# demeter_v26.net
KiCad netlist of a schematic drawn in EAGLE
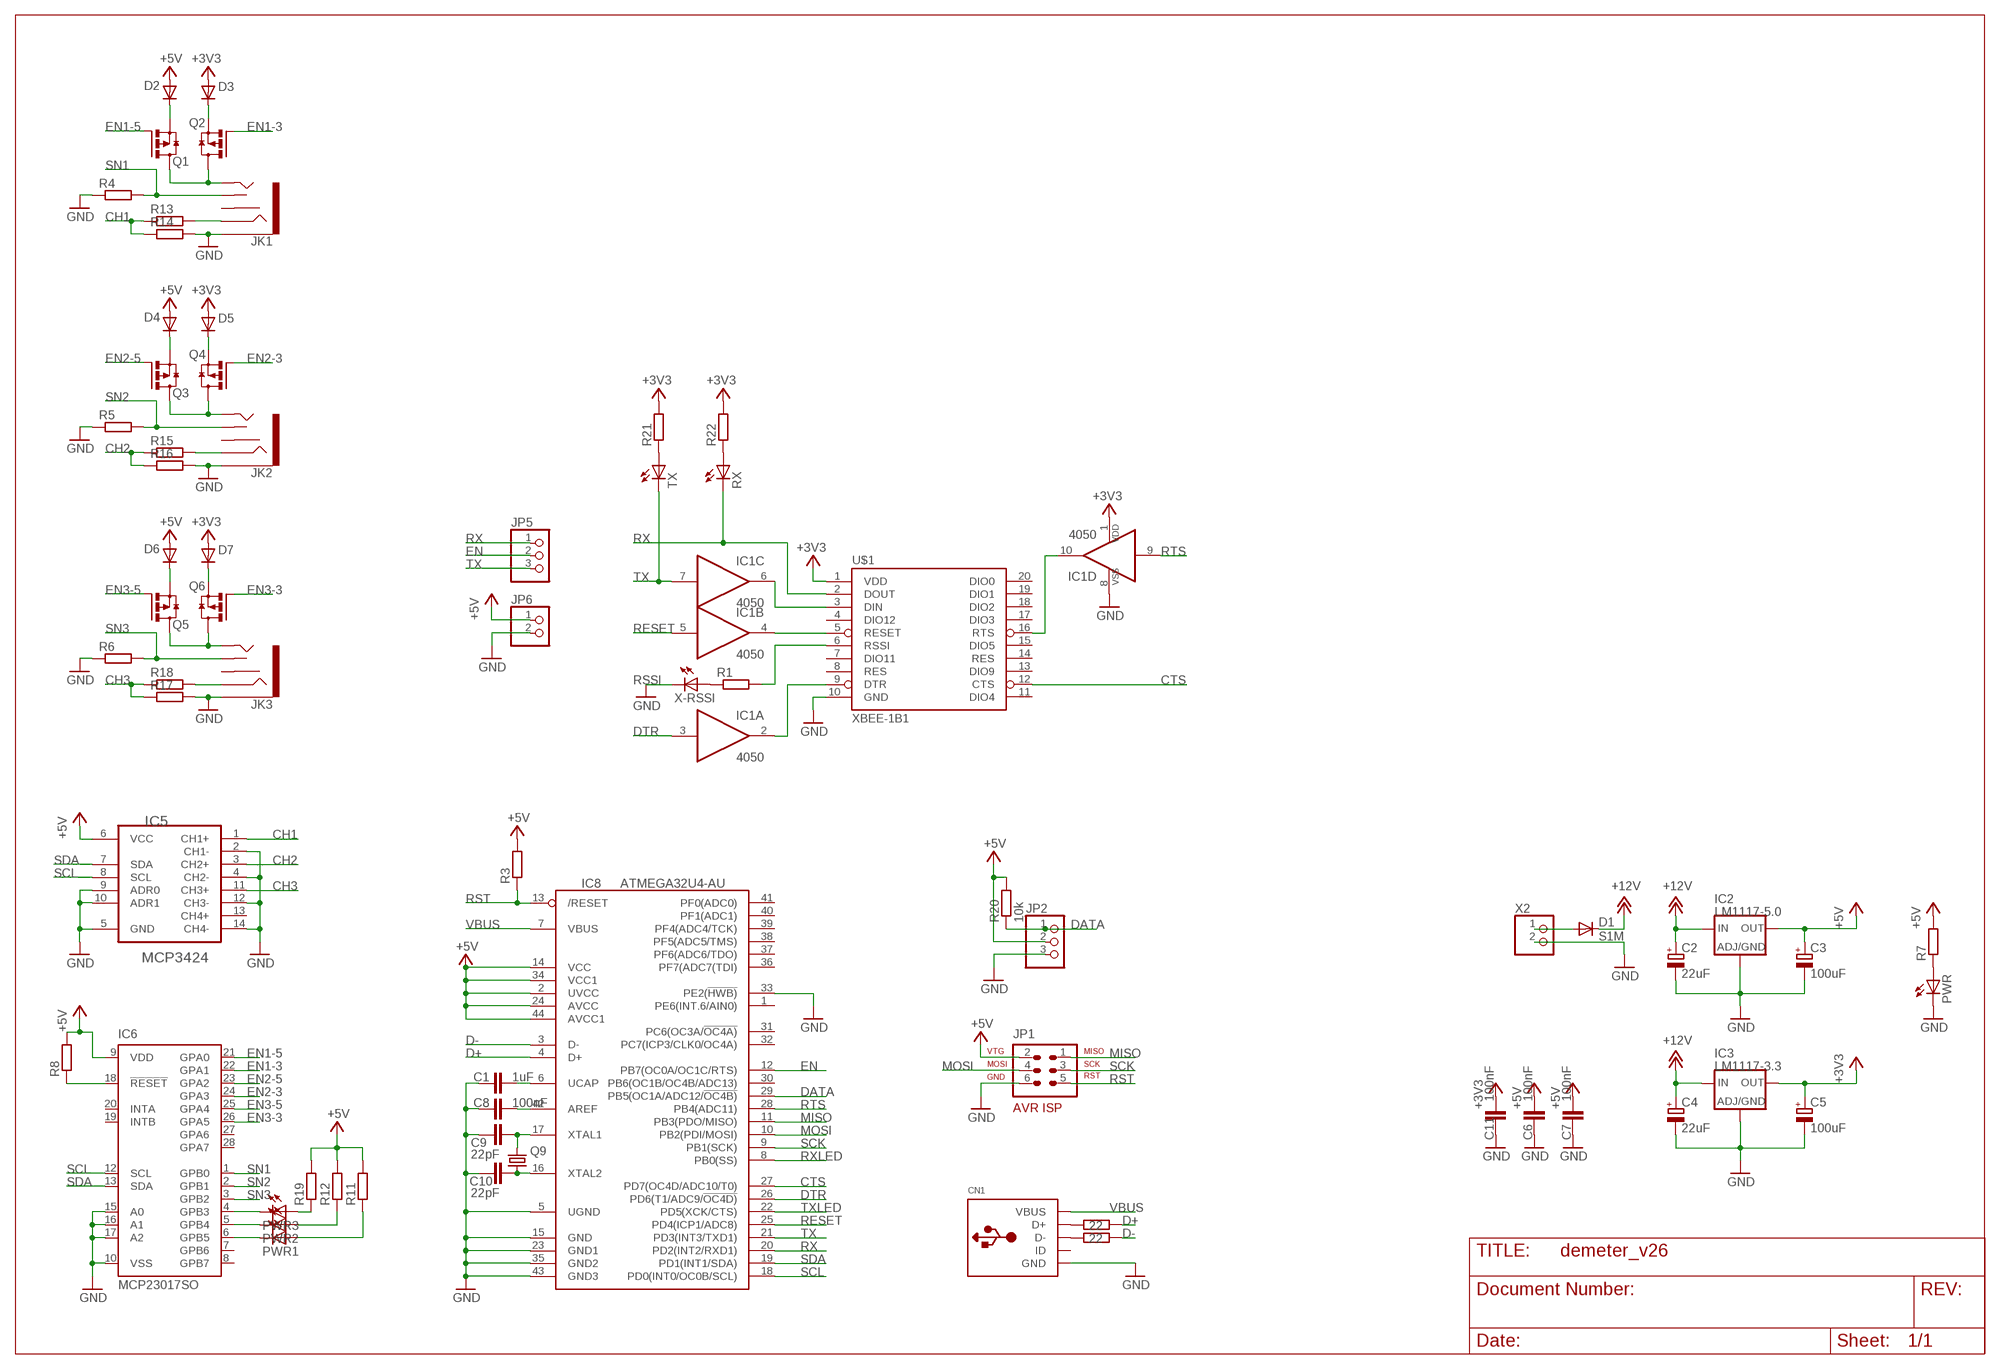
[diagram p0: schematic, sheet 1]

(export (version "E")
  (design (tool "Eeschema 10.0.6"))
  (components
    (comp (ref "C1")
      (value "1uF")
      (footprint "eagle-import:C0805K")
      (libsource (lib "eagle-import") (part "C-EUC0805K"))
    )
    (comp (ref "C2")
      (value "22uF")
      (footprint "eagle-import:PANASONIC_D")
      (libsource (lib "eagle-import") (part "CPOL-EUPD"))
    )
    (comp (ref "C3")
      (value "100uF")
      (footprint "eagle-import:PANASONIC_D")
      (libsource (lib "eagle-import") (part "CPOL-EUPD"))
    )
    (comp (ref "C4")
      (value "22uF")
      (footprint "eagle-import:PANASONIC_D")
      (libsource (lib "eagle-import") (part "CPOL-EUPD"))
    )
    (comp (ref "C5")
      (value "100uF")
      (footprint "eagle-import:PANASONIC_D")
      (libsource (lib "eagle-import") (part "CPOL-EUPD"))
    )
    (comp (ref "C6")
      (value "100nF")
      (footprint "eagle-import:C0805K")
      (libsource (lib "eagle-import") (part "C-EUC0805K"))
    )
    (comp (ref "C7")
      (value "100nF")
      (footprint "eagle-import:C0805K")
      (libsource (lib "eagle-import") (part "C-EUC0805K"))
    )
    (comp (ref "C8")
      (value "100nF")
      (footprint "eagle-import:C0805K")
      (libsource (lib "eagle-import") (part "C-EUC0805K"))
    )
    (comp (ref "C9")
      (value "22pF")
      (footprint "eagle-import:C0805K")
      (libsource (lib "eagle-import") (part "C-EUC0805K"))
    )
    (comp (ref "C10")
      (value "22pF")
      (footprint "eagle-import:C0805K")
      (libsource (lib "eagle-import") (part "C-EUC0805K"))
    )
    (comp (ref "C11")
      (value "100nF")
      (footprint "eagle-import:C0805K")
      (libsource (lib "eagle-import") (part "C-EUC0805K"))
    )
    (comp (ref "CN1")
      (value "USBMINIB")
      (footprint "eagle-import:USB-MINIB")
      (libsource (lib "eagle-import") (part "USBMINIB"))
    )
    (comp (ref "D1")
      (value "S1M")
      (footprint "eagle-import:DO-214AC")
      (libsource (lib "eagle-import") (part "S1M"))
    )
    (comp (ref "D2")
      (value "MBR0520")
      (footprint "eagle-import:SOD123")
      (libsource (lib "eagle-import") (part "MBR0520"))
    )
    (comp (ref "D3")
      (value "MBR0520")
      (footprint "eagle-import:SOD123")
      (libsource (lib "eagle-import") (part "MBR0520"))
    )
    (comp (ref "D4")
      (value "MBR0520")
      (footprint "eagle-import:SOD123")
      (libsource (lib "eagle-import") (part "MBR0520"))
    )
    (comp (ref "D5")
      (value "MBR0520")
      (footprint "eagle-import:SOD123")
      (libsource (lib "eagle-import") (part "MBR0520"))
    )
    (comp (ref "D6")
      (value "MBR0520")
      (footprint "eagle-import:SOD123")
      (libsource (lib "eagle-import") (part "MBR0520"))
    )
    (comp (ref "D7")
      (value "MBR0520")
      (footprint "eagle-import:SOD123")
      (libsource (lib "eagle-import") (part "MBR0520"))
    )
    (comp (ref "IC1")
      (value "4050")
      (footprint "eagle-import:SO16")
      (libsource (lib "eagle-import") (part "4050D"))
    )
    (comp (ref "IC2")
      (value "LM1117-5.0")
      (footprint "eagle-import:DPACK")
      (libsource (lib "eagle-import") (part "LM1117DT"))
    )
    (comp (ref "IC3")
      (value "LM1117-3.3")
      (footprint "eagle-import:DPACK")
      (libsource (lib "eagle-import") (part "LM1117DT"))
    )
    (comp (ref "IC5")
      (value "MCP3424")
      (footprint "eagle-import:SO14")
      (fields (field (name "MPN") "MCP3424-E/SL"))
      (libsource (lib "eagle-import") (part "MCP3424"))
    )
    (comp (ref "IC6")
      (value "MCP23017SO")
      (footprint "eagle-import:SO28W")
      (fields (field (name "MF") "MICROCHIP") (field (name "MPN") "MCP23017-E/SO"))
      (libsource (lib "eagle-import") (part "MCP23017SO"))
    )
    (comp (ref "IC8")
      (value "ATMEGA32U4-AU")
      (footprint "eagle-import:TQFP44")
      (libsource (lib "eagle-import") (part "ATMEGA32U4-AU"))
    )
    (comp (ref "JK1")
      (value "AUDIO-JACK2PTH")
      (footprint "eagle-import:AUDIO-JACK")
      (libsource (lib "eagle-import") (part "AUDIO-JACK2PTH"))
    )
    (comp (ref "JK2")
      (value "AUDIO-JACK2PTH")
      (footprint "eagle-import:AUDIO-JACK")
      (libsource (lib "eagle-import") (part "AUDIO-JACK2PTH"))
    )
    (comp (ref "JK3")
      (value "AUDIO-JACK2PTH")
      (footprint "eagle-import:AUDIO-JACK")
      (libsource (lib "eagle-import") (part "AUDIO-JACK2PTH"))
    )
    (comp (ref "JP1")
      (value "AVR-ISP-6")
      (footprint "eagle-import:AVR-ISP-6")
      (libsource (lib "eagle-import") (part "AVR-ISP-6"))
    )
    (comp (ref "JP2")
      (value "PINHD-1X3180")
      (footprint "eagle-import:1X03")
      (libsource (lib "eagle-import") (part "PINHD-1X3180"))
    )
    (comp (ref "JP5")
      (value "PINHD-1X3180")
      (footprint "eagle-import:1X03")
      (libsource (lib "eagle-import") (part "PINHD-1X3180"))
    )
    (comp (ref "JP6")
      (value "PINHD-1X2")
      (footprint "eagle-import:1X02")
      (libsource (lib "eagle-import") (part "PINHD-1X2"))
    )
    (comp (ref "PWR")
      (value "LED0805")
      (footprint "eagle-import:CHIP-LED0805")
      (libsource (lib "eagle-import") (part "LED0805"))
    )
    (comp (ref "PWR1")
      (value "LED0805")
      (footprint "eagle-import:CHIP-LED0805")
      (libsource (lib "eagle-import") (part "LED0805"))
    )
    (comp (ref "PWR2")
      (value "LED0805")
      (footprint "eagle-import:CHIP-LED0805")
      (libsource (lib "eagle-import") (part "LED0805"))
    )
    (comp (ref "PWR3")
      (value "LED0805")
      (footprint "eagle-import:CHIP-LED0805")
      (libsource (lib "eagle-import") (part "LED0805"))
    )
    (comp (ref "Q1")
      (value "IRLML6402")
      (footprint "eagle-import:SOT23")
      (libsource (lib "eagle-import") (part "IRLML6402"))
    )
    (comp (ref "Q2")
      (value "IRLML6402")
      (footprint "eagle-import:SOT23")
      (libsource (lib "eagle-import") (part "IRLML6402"))
    )
    (comp (ref "Q3")
      (value "IRLML6402")
      (footprint "eagle-import:SOT23")
      (libsource (lib "eagle-import") (part "IRLML6402"))
    )
    (comp (ref "Q4")
      (value "IRLML6402")
      (footprint "eagle-import:SOT23")
      (libsource (lib "eagle-import") (part "IRLML6402"))
    )
    (comp (ref "Q5")
      (value "IRLML6402")
      (footprint "eagle-import:SOT23")
      (libsource (lib "eagle-import") (part "IRLML6402"))
    )
    (comp (ref "Q6")
      (value "IRLML6402")
      (footprint "eagle-import:SOT23")
      (libsource (lib "eagle-import") (part "IRLML6402"))
    )
    (comp (ref "Q9")
      (value "CRYSTALHC49UP")
      (footprint "eagle-import:HC49UP")
      (libsource (lib "eagle-import") (part "CRYSTALHC49UP"))
    )
    (comp (ref "R1")
      (value "R-EU_R0805")
      (footprint "eagle-import:R0805")
      (libsource (lib "eagle-import") (part "R-EU_R0805"))
    )
    (comp (ref "R3")
      (value "R-EU_R0805")
      (footprint "eagle-import:R0805")
      (libsource (lib "eagle-import") (part "R-EU_R0805"))
    )
    (comp (ref "R4")
      (value "R-EU_R0805")
      (footprint "eagle-import:R0805")
      (libsource (lib "eagle-import") (part "R-EU_R0805"))
    )
    (comp (ref "R5")
      (value "R-EU_R0805")
      (footprint "eagle-import:R0805")
      (libsource (lib "eagle-import") (part "R-EU_R0805"))
    )
    (comp (ref "R6")
      (value "R-EU_R0805")
      (footprint "eagle-import:R0805")
      (libsource (lib "eagle-import") (part "R-EU_R0805"))
    )
    (comp (ref "R7")
      (value "R-EU_R0805")
      (footprint "eagle-import:R0805")
      (libsource (lib "eagle-import") (part "R-EU_R0805"))
    )
    (comp (ref "R8")
      (value "R-EU_R0805")
      (footprint "eagle-import:R0805")
      (libsource (lib "eagle-import") (part "R-EU_R0805"))
    )
    (comp (ref "R9")
      (value "22")
      (footprint "eagle-import:R0805")
      (libsource (lib "eagle-import") (part "R-EU_R0805"))
    )
    (comp (ref "R10")
      (value "22")
      (footprint "eagle-import:R0805")
      (libsource (lib "eagle-import") (part "R-EU_R0805"))
    )
    (comp (ref "R11")
      (value "R-EU_R0805")
      (footprint "eagle-import:R0805")
      (libsource (lib "eagle-import") (part "R-EU_R0805"))
    )
    (comp (ref "R12")
      (value "R-EU_R0805")
      (footprint "eagle-import:R0805")
      (libsource (lib "eagle-import") (part "R-EU_R0805"))
    )
    (comp (ref "R13")
      (value "R-EU_R0805")
      (footprint "eagle-import:R0805")
      (libsource (lib "eagle-import") (part "R-EU_R0805"))
    )
    (comp (ref "R14")
      (value "R-EU_R0805")
      (footprint "eagle-import:R0805")
      (libsource (lib "eagle-import") (part "R-EU_R0805"))
    )
    (comp (ref "R15")
      (value "R-EU_R0805")
      (footprint "eagle-import:R0805")
      (libsource (lib "eagle-import") (part "R-EU_R0805"))
    )
    (comp (ref "R16")
      (value "R-EU_R0805")
      (footprint "eagle-import:R0805")
      (libsource (lib "eagle-import") (part "R-EU_R0805"))
    )
    (comp (ref "R17")
      (value "R-EU_R0805")
      (footprint "eagle-import:R0805")
      (libsource (lib "eagle-import") (part "R-EU_R0805"))
    )
    (comp (ref "R18")
      (value "R-EU_R0805")
      (footprint "eagle-import:R0805")
      (libsource (lib "eagle-import") (part "R-EU_R0805"))
    )
    (comp (ref "R19")
      (value "R-EU_R0805")
      (footprint "eagle-import:R0805")
      (libsource (lib "eagle-import") (part "R-EU_R0805"))
    )
    (comp (ref "R20")
      (value "10k")
      (footprint "eagle-import:R0805")
      (libsource (lib "eagle-import") (part "R-EU_R0805"))
    )
    (comp (ref "R21")
      (value "R-EU_R0805")
      (footprint "eagle-import:R0805")
      (libsource (lib "eagle-import") (part "R-EU_R0805"))
    )
    (comp (ref "R22")
      (value "R-EU_R0805")
      (footprint "eagle-import:R0805")
      (libsource (lib "eagle-import") (part "R-EU_R0805"))
    )
    (comp (ref "RX")
      (value "LED0805")
      (footprint "eagle-import:CHIP-LED0805")
      (libsource (lib "eagle-import") (part "LED0805"))
    )
    (comp (ref "TX")
      (value "LED0805")
      (footprint "eagle-import:CHIP-LED0805")
      (libsource (lib "eagle-import") (part "LED0805"))
    )
    (comp (ref "U$1")
      (value "XBEE-1B1")
      (footprint "eagle-import:XBEE-1")
      (libsource (lib "eagle-import") (part "XBEE-1B1"))
    )
    (comp (ref "X-RSSI")
      (value "LED0805")
      (footprint "eagle-import:CHIP-LED0805")
      (libsource (lib "eagle-import") (part "LED0805"))
    )
    (comp (ref "X2")
      (value "W237-102")
      (footprint "eagle-import:W237-102")
      (libsource (lib "eagle-import") (part "W237-102"))
    )
  )
  (nets
    (net (code "1") (name "+3V3") (class "Default")
      (node (ref "C11") (pin "1") (pinfunction "1_1") (pintype "passive"))
      (node (ref "C5") (pin "+") (pinfunction "+_+") (pintype "passive"))
      (node (ref "D3") (pin "A") (pinfunction "A_A") (pintype "passive"))
      (node (ref "D5") (pin "A") (pinfunction "A_A") (pintype "passive"))
      (node (ref "D7") (pin "A") (pinfunction "A_A") (pintype "passive"))
      (node (ref "IC1") (pin "1") (pinfunction "VDD_1") (pintype "power_in"))
      (node (ref "IC3") (pin "4") (pinfunction "OUT_4") (pintype "passive"))
      (node (ref "R21") (pin "2") (pinfunction "2_2") (pintype "passive"))
      (node (ref "R22") (pin "2") (pinfunction "2_2") (pintype "passive"))
      (node (ref "U$1") (pin "1") (pinfunction "VDD_1") (pintype "power_in"))
    )
    (net (code "2") (name "+5V") (class "Default")
      (node (ref "C3") (pin "+") (pinfunction "+_+") (pintype "passive"))
      (node (ref "C6") (pin "1") (pinfunction "1_1") (pintype "passive"))
      (node (ref "C7") (pin "1") (pinfunction "1_1") (pintype "passive"))
      (node (ref "D2") (pin "A") (pinfunction "A_A") (pintype "passive"))
      (node (ref "D4") (pin "A") (pinfunction "A_A") (pintype "passive"))
      (node (ref "D6") (pin "A") (pinfunction "A_A") (pintype "passive"))
      (node (ref "IC2") (pin "4") (pinfunction "OUT_4") (pintype "passive"))
      (node (ref "IC5") (pin "6") (pinfunction "VCC_6") (pintype "power_in"))
      (node (ref "IC6") (pin "9") (pinfunction "VDD_9") (pintype "power_in"))
      (node (ref "IC8") (pin "14") (pinfunction "VCC_14") (pintype "bidirectional"))
      (node (ref "IC8") (pin "2") (pinfunction "UVCC_2") (pintype "bidirectional"))
      (node (ref "IC8") (pin "24") (pinfunction "AVCC_24") (pintype "bidirectional"))
      (node (ref "IC8") (pin "34") (pinfunction "VCC1_34") (pintype "bidirectional"))
      (node (ref "IC8") (pin "44") (pinfunction "AVCC1_44") (pintype "bidirectional"))
      (node (ref "JP1") (pin "2") (pinfunction "VTG_2") (pintype "passive"))
      (node (ref "JP2") (pin "2") (pinfunction "2_2") (pintype "passive"))
      (node (ref "JP6") (pin "1") (pinfunction "1_1") (pintype "passive"))
      (node (ref "R11") (pin "2") (pinfunction "2_2") (pintype "passive"))
      (node (ref "R12") (pin "2") (pinfunction "2_2") (pintype "passive"))
      (node (ref "R19") (pin "2") (pinfunction "2_2") (pintype "passive"))
      (node (ref "R20") (pin "2") (pinfunction "2_2") (pintype "passive"))
      (node (ref "R3") (pin "2") (pinfunction "2_2") (pintype "passive"))
      (node (ref "R7") (pin "2") (pinfunction "2_2") (pintype "passive"))
      (node (ref "R8") (pin "2") (pinfunction "2_2") (pintype "passive"))
    )
    (net (code "3") (name "+12V") (class "Default")
      (node (ref "C2") (pin "+") (pinfunction "+_+") (pintype "passive"))
      (node (ref "C4") (pin "+") (pinfunction "+_+") (pintype "passive"))
      (node (ref "D1") (pin "C") (pinfunction "C_C") (pintype "passive"))
      (node (ref "IC2") (pin "3") (pinfunction "IN_3") (pintype "input"))
      (node (ref "IC3") (pin "3") (pinfunction "IN_3") (pintype "input"))
    )
    (net (code "4") (name "/CH1") (class "Default")
      (node (ref "IC5") (pin "1") (pinfunction "CH1+_1") (pintype "input"))
      (node (ref "R13") (pin "1") (pinfunction "1_1") (pintype "passive"))
      (node (ref "R14") (pin "1") (pinfunction "1_1") (pintype "passive"))
    )
    (net (code "5") (name "/CH2") (class "Default")
      (node (ref "IC5") (pin "3") (pinfunction "CH2+_3") (pintype "input"))
      (node (ref "R15") (pin "1") (pinfunction "1_1") (pintype "passive"))
      (node (ref "R16") (pin "1") (pinfunction "1_1") (pintype "passive"))
    )
    (net (code "6") (name "/CH3") (class "Default")
      (node (ref "IC5") (pin "11") (pinfunction "CH3+_11") (pintype "input"))
      (node (ref "R17") (pin "1") (pinfunction "1_1") (pintype "passive"))
      (node (ref "R18") (pin "1") (pinfunction "1_1") (pintype "passive"))
    )
    (net (code "7") (name "/CTS") (class "Default")
      (node (ref "IC8") (pin "27") (pinfunction "PD7(OC4D/ADC10/T0)_27") (pintype "bidirectional"))
      (node (ref "U$1") (pin "12") (pinfunction "CTS_12") (pintype "output"))
    )
    (net (code "8") (name "/D+") (class "Default")
      (node (ref "IC8") (pin "4") (pinfunction "D+_4") (pintype "bidirectional"))
      (node (ref "R9") (pin "1") (pinfunction "1_1") (pintype "passive"))
    )
    (net (code "9") (name "/D-") (class "Default")
      (node (ref "IC8") (pin "3") (pinfunction "D-_3") (pintype "bidirectional"))
      (node (ref "R10") (pin "1") (pinfunction "1_1") (pintype "passive"))
    )
    (net (code "10") (name "/DATA") (class "Default")
      (node (ref "IC8") (pin "29") (pinfunction "PB5(OC1A/ADC12/~{OC4B})_29") (pintype "bidirectional"))
      (node (ref "JP2") (pin "1") (pinfunction "1_1") (pintype "passive"))
      (node (ref "R20") (pin "1") (pinfunction "1_1") (pintype "passive"))
    )
    (net (code "11") (name "/DTR") (class "Default")
      (node (ref "IC1") (pin "3") (pinfunction "I_3") (pintype "input"))
      (node (ref "IC8") (pin "26") (pinfunction "PD6(T1/ADC9/~{OC4D})_26") (pintype "bidirectional"))
    )
    (net (code "12") (name "/EN") (class "Default")
      (node (ref "IC8") (pin "12") (pinfunction "PB7(OC0A/OC1C/RTS)_12") (pintype "bidirectional"))
      (node (ref "JP5") (pin "2") (pinfunction "2_2") (pintype "passive"))
    )
    (net (code "13") (name "/EN1-3") (class "Default")
      (node (ref "IC6") (pin "22") (pinfunction "GPA1_22") (pintype "bidirectional"))
      (node (ref "Q2") (pin "1") (pinfunction "G_1") (pintype "passive"))
    )
    (net (code "14") (name "/EN1-5") (class "Default")
      (node (ref "IC6") (pin "21") (pinfunction "GPA0_21") (pintype "bidirectional"))
      (node (ref "Q1") (pin "1") (pinfunction "G_1") (pintype "passive"))
    )
    (net (code "15") (name "/EN2-3") (class "Default")
      (node (ref "IC6") (pin "24") (pinfunction "GPA3_24") (pintype "bidirectional"))
      (node (ref "Q4") (pin "1") (pinfunction "G_1") (pintype "passive"))
    )
    (net (code "16") (name "/EN2-5") (class "Default")
      (node (ref "IC6") (pin "23") (pinfunction "GPA2_23") (pintype "bidirectional"))
      (node (ref "Q3") (pin "1") (pinfunction "G_1") (pintype "passive"))
    )
    (net (code "17") (name "/EN3-3") (class "Default")
      (node (ref "IC6") (pin "26") (pinfunction "GPA5_26") (pintype "bidirectional"))
      (node (ref "Q6") (pin "1") (pinfunction "G_1") (pintype "passive"))
    )
    (net (code "18") (name "/EN3-5") (class "Default")
      (node (ref "IC6") (pin "25") (pinfunction "GPA4_25") (pintype "bidirectional"))
      (node (ref "Q5") (pin "1") (pinfunction "G_1") (pintype "passive"))
    )
    (net (code "19") (name "/MISO") (class "Default")
      (node (ref "IC8") (pin "11") (pinfunction "PB3(PDO/MISO)_11") (pintype "bidirectional"))
      (node (ref "JP1") (pin "1") (pinfunction "MISO_1") (pintype "passive"))
    )
    (net (code "20") (name "/MOSI") (class "Default")
      (node (ref "IC8") (pin "10") (pinfunction "PB2(PDI/MOSI)_10") (pintype "bidirectional"))
      (node (ref "JP1") (pin "4") (pinfunction "MOSI_4") (pintype "passive"))
    )
    (net (code "21") (name "/RESET") (class "Default")
      (node (ref "IC1") (pin "5") (pinfunction "I_5") (pintype "input"))
      (node (ref "IC8") (pin "25") (pinfunction "PD4(ICP1/ADC8)_25") (pintype "bidirectional"))
    )
    (net (code "22") (name "/RSSI") (class "Default")
      (node (ref "R1") (pin "2") (pinfunction "2_2") (pintype "passive"))
      (node (ref "U$1") (pin "6") (pinfunction "RSSI_6") (pintype "bidirectional"))
    )
    (net (code "23") (name "/RST") (class "Default")
      (node (ref "IC8") (pin "13") (pinfunction "/RESET_13") (pintype "bidirectional"))
      (node (ref "JP1") (pin "5") (pinfunction "RST_5") (pintype "passive"))
      (node (ref "R3") (pin "1") (pinfunction "1_1") (pintype "passive"))
    )
    (net (code "24") (name "/RTS") (class "Default")
      (node (ref "IC1") (pin "9") (pinfunction "I_9") (pintype "input"))
      (node (ref "IC8") (pin "28") (pinfunction "PB4(ADC11)_28") (pintype "bidirectional"))
    )
    (net (code "25") (name "/RX") (class "Default")
      (node (ref "IC8") (pin "20") (pinfunction "PD2(INT2/RXD1)_20") (pintype "bidirectional"))
      (node (ref "JP5") (pin "1") (pinfunction "1_1") (pintype "passive"))
      (node (ref "RX") (pin "C") (pinfunction "C_C") (pintype "passive"))
      (node (ref "U$1") (pin "2") (pinfunction "DOUT_2") (pintype "output"))
    )
    (net (code "26") (name "/RXLED") (class "Default")
      (node (ref "IC8") (pin "8") (pinfunction "PB0(SS)_8") (pintype "bidirectional"))
    )
    (net (code "27") (name "/SCK") (class "Default")
      (node (ref "IC8") (pin "9") (pinfunction "PB1(SCK)_9") (pintype "bidirectional"))
      (node (ref "JP1") (pin "3") (pinfunction "SCK_3") (pintype "passive"))
    )
    (net (code "28") (name "/SCL") (class "Default")
      (node (ref "IC5") (pin "8") (pinfunction "SCL_8") (pintype "input"))
      (node (ref "IC6") (pin "12") (pinfunction "SCL_12") (pintype "input"))
      (node (ref "IC8") (pin "18") (pinfunction "PD0(INT0/OC0B/SCL)_18") (pintype "bidirectional"))
    )
    (net (code "29") (name "/SDA") (class "Default")
      (node (ref "IC5") (pin "7") (pinfunction "SDA_7") (pintype "bidirectional"))
      (node (ref "IC6") (pin "13") (pinfunction "SDA_13") (pintype "bidirectional"))
      (node (ref "IC8") (pin "19") (pinfunction "PD1(INT1/SDA)_19") (pintype "bidirectional"))
    )
    (net (code "30") (name "/SN1") (class "Default")
      (node (ref "IC6") (pin "1") (pinfunction "GPB0_1") (pintype "bidirectional"))
      (node (ref "JK1") (pin "TSH") (pinfunction "TSH_TSH") (pintype "bidirectional"))
      (node (ref "R4") (pin "2") (pinfunction "2_2") (pintype "passive"))
    )
    (net (code "31") (name "/SN2") (class "Default")
      (node (ref "IC6") (pin "2") (pinfunction "GPB1_2") (pintype "bidirectional"))
      (node (ref "JK2") (pin "TSH") (pinfunction "TSH_TSH") (pintype "bidirectional"))
      (node (ref "R5") (pin "2") (pinfunction "2_2") (pintype "passive"))
    )
    (net (code "32") (name "/SN3") (class "Default")
      (node (ref "IC6") (pin "3") (pinfunction "GPB2_3") (pintype "bidirectional"))
      (node (ref "JK3") (pin "TSH") (pinfunction "TSH_TSH") (pintype "bidirectional"))
      (node (ref "R6") (pin "2") (pinfunction "2_2") (pintype "passive"))
    )
    (net (code "33") (name "/TX") (class "Default")
      (node (ref "IC1") (pin "7") (pinfunction "I_7") (pintype "input"))
      (node (ref "IC8") (pin "21") (pinfunction "PD3(INT3/TXD1)_21") (pintype "bidirectional"))
      (node (ref "JP5") (pin "3") (pinfunction "3_3") (pintype "passive"))
      (node (ref "TX") (pin "C") (pinfunction "C_C") (pintype "passive"))
    )
    (net (code "34") (name "/TXLED") (class "Default")
      (node (ref "IC8") (pin "22") (pinfunction "PD5(XCK/CTS)_22") (pintype "bidirectional"))
    )
    (net (code "35") (name "/VBUS") (class "Default")
      (node (ref "CN1") (pin "VBUS") (pinfunction "VBUS_VBUS") (pintype "power_in"))
      (node (ref "IC8") (pin "7") (pinfunction "VBUS_7") (pintype "bidirectional"))
    )
    (net (code "36") (name "GND") (class "Default")
      (node (ref "C1") (pin "2") (pinfunction "2_2") (pintype "passive"))
      (node (ref "C10") (pin "2") (pinfunction "2_2") (pintype "passive"))
      (node (ref "C11") (pin "2") (pinfunction "2_2") (pintype "passive"))
      (node (ref "C2") (pin "-") (pinfunction "-_-") (pintype "passive"))
      (node (ref "C3") (pin "-") (pinfunction "-_-") (pintype "passive"))
      (node (ref "C4") (pin "-") (pinfunction "-_-") (pintype "passive"))
      (node (ref "C5") (pin "-") (pinfunction "-_-") (pintype "passive"))
      (node (ref "C6") (pin "2") (pinfunction "2_2") (pintype "passive"))
      (node (ref "C7") (pin "2") (pinfunction "2_2") (pintype "passive"))
      (node (ref "C8") (pin "2") (pinfunction "2_2") (pintype "passive"))
      (node (ref "C9") (pin "2") (pinfunction "2_2") (pintype "passive"))
      (node (ref "CN1") (pin "GND") (pinfunction "GND_GND") (pintype "power_in"))
      (node (ref "IC1") (pin "8") (pinfunction "VSS_8") (pintype "power_in"))
      (node (ref "IC2") (pin "1") (pinfunction "ADJ_1") (pintype "input"))
      (node (ref "IC3") (pin "1") (pinfunction "ADJ_1") (pintype "input"))
      (node (ref "IC5") (pin "10") (pinfunction "ADR1_10") (pintype "input"))
      (node (ref "IC5") (pin "12") (pinfunction "CH3-_12") (pintype "input"))
      (node (ref "IC5") (pin "14") (pinfunction "CH4-_14") (pintype "input"))
      (node (ref "IC5") (pin "2") (pinfunction "CH1-_2") (pintype "input"))
      (node (ref "IC5") (pin "4") (pinfunction "CH2-_4") (pintype "input"))
      (node (ref "IC5") (pin "5") (pinfunction "GND_5") (pintype "power_in"))
      (node (ref "IC5") (pin "9") (pinfunction "ADR0_9") (pintype "input"))
      (node (ref "IC6") (pin "10") (pinfunction "VSS_10") (pintype "power_in"))
      (node (ref "IC6") (pin "15") (pinfunction "A0_15") (pintype "input"))
      (node (ref "IC6") (pin "16") (pinfunction "A1_16") (pintype "input"))
      (node (ref "IC6") (pin "17") (pinfunction "A2_17") (pintype "input"))
      (node (ref "IC8") (pin "15") (pinfunction "GND_15") (pintype "bidirectional"))
      (node (ref "IC8") (pin "23") (pinfunction "GND1_23") (pintype "bidirectional"))
      (node (ref "IC8") (pin "33") (pinfunction "PE2(~{HWB})_33") (pintype "bidirectional"))
      (node (ref "IC8") (pin "35") (pinfunction "GND2_35") (pintype "bidirectional"))
      (node (ref "IC8") (pin "43") (pinfunction "GND3_43") (pintype "bidirectional"))
      (node (ref "IC8") (pin "5") (pinfunction "UGND_5") (pintype "bidirectional"))
      (node (ref "JK1") (pin "SLEEVE") (pinfunction "SLEEVE_SLEEVE") (pintype "bidirectional"))
      (node (ref "JK2") (pin "SLEEVE") (pinfunction "SLEEVE_SLEEVE") (pintype "bidirectional"))
      (node (ref "JK3") (pin "SLEEVE") (pinfunction "SLEEVE_SLEEVE") (pintype "bidirectional"))
      (node (ref "JP1") (pin "6") (pinfunction "GND_6") (pintype "passive"))
      (node (ref "JP2") (pin "3") (pinfunction "3_3") (pintype "passive"))
      (node (ref "JP6") (pin "2") (pinfunction "2_2") (pintype "passive"))
      (node (ref "PWR") (pin "C") (pinfunction "C_C") (pintype "passive"))
      (node (ref "R14") (pin "2") (pinfunction "2_2") (pintype "passive"))
      (node (ref "R16") (pin "2") (pinfunction "2_2") (pintype "passive"))
      (node (ref "R17") (pin "2") (pinfunction "2_2") (pintype "passive"))
      (node (ref "R4") (pin "1") (pinfunction "1_1") (pintype "passive"))
      (node (ref "R5") (pin "1") (pinfunction "1_1") (pintype "passive"))
      (node (ref "R6") (pin "1") (pinfunction "1_1") (pintype "passive"))
      (node (ref "U$1") (pin "10") (pinfunction "GND_10") (pintype "power_in"))
      (node (ref "X-RSSI") (pin "C") (pinfunction "C_C") (pintype "passive"))
      (node (ref "X2") (pin "2") (pinfunction "2_2") (pintype "passive"))
    )
    (net (code "37") (name "Net-(CN1-PadD+)") (class "Default")
      (node (ref "CN1") (pin "D+") (pinfunction "D+_D+") (pintype "bidirectional"))
      (node (ref "R9") (pin "2") (pinfunction "2_2") (pintype "passive"))
    )
    (net (code "38") (name "Net-(CN1-PadD-)") (class "Default")
      (node (ref "CN1") (pin "D-") (pinfunction "D-_D-") (pintype "bidirectional"))
      (node (ref "R10") (pin "2") (pinfunction "2_2") (pintype "passive"))
    )
    (net (code "39") (name "Net-(D1-PadA)") (class "Default")
      (node (ref "D1") (pin "A") (pinfunction "A_A") (pintype "passive"))
      (node (ref "X2") (pin "1") (pinfunction "1_1") (pintype "passive"))
    )
    (net (code "40") (name "Net-(IC1A-O)") (class "Default")
      (node (ref "IC1") (pin "2") (pinfunction "O_2") (pintype "output"))
      (node (ref "U$1") (pin "9") (pinfunction "DTR_9") (pintype "bidirectional"))
    )
    (net (code "41") (name "Net-(IC1B-O)") (class "Default")
      (node (ref "IC1") (pin "4") (pinfunction "O_4") (pintype "output"))
      (node (ref "U$1") (pin "5") (pinfunction "RESET_5") (pintype "input"))
    )
    (net (code "42") (name "Net-(IC1C-O)") (class "Default")
      (node (ref "IC1") (pin "6") (pinfunction "O_6") (pintype "output"))
      (node (ref "U$1") (pin "3") (pinfunction "DIN_3") (pintype "input"))
    )
    (net (code "43") (name "Net-(IC1D-O)") (class "Default")
      (node (ref "IC1") (pin "10") (pinfunction "O_10") (pintype "output"))
      (node (ref "U$1") (pin "16") (pinfunction "RTS_16") (pintype "input"))
    )
    (net (code "44") (name "Net-(IC6-GPB3)") (class "Default")
      (node (ref "IC6") (pin "4") (pinfunction "GPB3_4") (pintype "bidirectional"))
      (node (ref "PWR3") (pin "C") (pinfunction "C_C") (pintype "passive"))
    )
    (net (code "45") (name "Net-(IC6-GPB4)") (class "Default")
      (node (ref "IC6") (pin "5") (pinfunction "GPB4_5") (pintype "bidirectional"))
      (node (ref "PWR2") (pin "C") (pinfunction "C_C") (pintype "passive"))
    )
    (net (code "46") (name "Net-(IC6-GPB5)") (class "Default")
      (node (ref "IC6") (pin "6") (pinfunction "GPB5_6") (pintype "bidirectional"))
      (node (ref "PWR1") (pin "C") (pinfunction "C_C") (pintype "passive"))
    )
    (net (code "47") (name "Net-(IC6-~{RESET})") (class "Default")
      (node (ref "IC6") (pin "18") (pinfunction "~{RESET}_18") (pintype "input"))
      (node (ref "R8") (pin "1") (pinfunction "1_1") (pintype "passive"))
    )
    (net (code "48") (name "Net-(IC8-AREF)") (class "Default")
      (node (ref "C8") (pin "1") (pinfunction "1_1") (pintype "passive"))
      (node (ref "IC8") (pin "42") (pinfunction "AREF_42") (pintype "bidirectional"))
    )
    (net (code "49") (name "Net-(IC8-UCAP)") (class "Default")
      (node (ref "C1") (pin "1") (pinfunction "1_1") (pintype "passive"))
      (node (ref "IC8") (pin "6") (pinfunction "UCAP_6") (pintype "bidirectional"))
    )
    (net (code "50") (name "Net-(IC8-XTAL1)") (class "Default")
      (node (ref "C9") (pin "1") (pinfunction "1_1") (pintype "passive"))
      (node (ref "IC8") (pin "17") (pinfunction "XTAL1_17") (pintype "bidirectional"))
      (node (ref "Q9") (pin "2") (pinfunction "2_2") (pintype "passive"))
    )
    (net (code "51") (name "Net-(IC8-XTAL2)") (class "Default")
      (node (ref "C10") (pin "1") (pinfunction "1_1") (pintype "passive"))
      (node (ref "IC8") (pin "16") (pinfunction "XTAL2_16") (pintype "bidirectional"))
      (node (ref "Q9") (pin "1") (pinfunction "1_1") (pintype "passive"))
    )
    (net (code "52") (name "Net-(JK1-PadRING)") (class "Default")
      (node (ref "JK1") (pin "RING") (pinfunction "RING_RING") (pintype "bidirectional"))
      (node (ref "R13") (pin "2") (pinfunction "2_2") (pintype "passive"))
    )
    (net (code "53") (name "Net-(JK2-PadRING)") (class "Default")
      (node (ref "JK2") (pin "RING") (pinfunction "RING_RING") (pintype "bidirectional"))
      (node (ref "R15") (pin "2") (pinfunction "2_2") (pintype "passive"))
    )
    (net (code "54") (name "Net-(JK3-PadRING)") (class "Default")
      (node (ref "JK3") (pin "RING") (pinfunction "RING_RING") (pintype "bidirectional"))
      (node (ref "R18") (pin "2") (pinfunction "2_2") (pintype "passive"))
    )
    (net (code "55") (name "Net-(PWR-PadA)") (class "Default")
      (node (ref "PWR") (pin "A") (pinfunction "A_A") (pintype "passive"))
      (node (ref "R7") (pin "1") (pinfunction "1_1") (pintype "passive"))
    )
    (net (code "56") (name "Net-(PWR1-PadA)") (class "Default")
      (node (ref "PWR1") (pin "A") (pinfunction "A_A") (pintype "passive"))
      (node (ref "R11") (pin "1") (pinfunction "1_1") (pintype "passive"))
    )
    (net (code "57") (name "Net-(PWR2-PadA)") (class "Default")
      (node (ref "PWR2") (pin "A") (pinfunction "A_A") (pintype "passive"))
      (node (ref "R12") (pin "1") (pinfunction "1_1") (pintype "passive"))
    )
    (net (code "58") (name "Net-(PWR3-PadA)") (class "Default")
      (node (ref "PWR3") (pin "A") (pinfunction "A_A") (pintype "passive"))
      (node (ref "R19") (pin "1") (pinfunction "1_1") (pintype "passive"))
    )
    (net (code "59") (name "Net-(Q1-D)") (class "Default")
      (node (ref "JK1") (pin "TIP") (pinfunction "TIP_TIP") (pintype "bidirectional"))
      (node (ref "Q1") (pin "3") (pinfunction "D_3") (pintype "passive"))
      (node (ref "Q2") (pin "3") (pinfunction "D_3") (pintype "passive"))
    )
    (net (code "60") (name "Net-(Q1-S)") (class "Default")
      (node (ref "D2") (pin "C") (pinfunction "C_C") (pintype "passive"))
      (node (ref "Q1") (pin "2") (pinfunction "S_2") (pintype "passive"))
    )
    (net (code "61") (name "Net-(Q2-S)") (class "Default")
      (node (ref "D3") (pin "C") (pinfunction "C_C") (pintype "passive"))
      (node (ref "Q2") (pin "2") (pinfunction "S_2") (pintype "passive"))
    )
    (net (code "62") (name "Net-(Q3-D)") (class "Default")
      (node (ref "JK2") (pin "TIP") (pinfunction "TIP_TIP") (pintype "bidirectional"))
      (node (ref "Q3") (pin "3") (pinfunction "D_3") (pintype "passive"))
      (node (ref "Q4") (pin "3") (pinfunction "D_3") (pintype "passive"))
    )
    (net (code "63") (name "Net-(Q3-S)") (class "Default")
      (node (ref "D4") (pin "C") (pinfunction "C_C") (pintype "passive"))
      (node (ref "Q3") (pin "2") (pinfunction "S_2") (pintype "passive"))
    )
    (net (code "64") (name "Net-(Q4-S)") (class "Default")
      (node (ref "D5") (pin "C") (pinfunction "C_C") (pintype "passive"))
      (node (ref "Q4") (pin "2") (pinfunction "S_2") (pintype "passive"))
    )
    (net (code "65") (name "Net-(Q5-D)") (class "Default")
      (node (ref "JK3") (pin "TIP") (pinfunction "TIP_TIP") (pintype "bidirectional"))
      (node (ref "Q5") (pin "3") (pinfunction "D_3") (pintype "passive"))
      (node (ref "Q6") (pin "3") (pinfunction "D_3") (pintype "passive"))
    )
    (net (code "66") (name "Net-(Q5-S)") (class "Default")
      (node (ref "D6") (pin "C") (pinfunction "C_C") (pintype "passive"))
      (node (ref "Q5") (pin "2") (pinfunction "S_2") (pintype "passive"))
    )
    (net (code "67") (name "Net-(Q6-S)") (class "Default")
      (node (ref "D7") (pin "C") (pinfunction "C_C") (pintype "passive"))
      (node (ref "Q6") (pin "2") (pinfunction "S_2") (pintype "passive"))
    )
    (net (code "68") (name "Net-(R1-Pad1)") (class "Default")
      (node (ref "R1") (pin "1") (pinfunction "1_1") (pintype "passive"))
      (node (ref "X-RSSI") (pin "A") (pinfunction "A_A") (pintype "passive"))
    )
    (net (code "69") (name "Net-(R21-Pad1)") (class "Default")
      (node (ref "R21") (pin "1") (pinfunction "1_1") (pintype "passive"))
      (node (ref "TX") (pin "A") (pinfunction "A_A") (pintype "passive"))
    )
    (net (code "70") (name "Net-(R22-Pad1)") (class "Default")
      (node (ref "R22") (pin "1") (pinfunction "1_1") (pintype "passive"))
      (node (ref "RX") (pin "A") (pinfunction "A_A") (pintype "passive"))
    )
    (net (code "71") (name "unconnected-(CN1-PadID)") (class "Default")
      (node (ref "CN1") (pin "ID") (pinfunction "ID_ID") (pintype "bidirectional"))
    )
    (net (code "72") (name "unconnected-(IC5-CH4+-Pad13)") (class "Default")
      (node (ref "IC5") (pin "13") (pinfunction "CH4+_13") (pintype "input"))
    )
    (net (code "73") (name "unconnected-(IC6-GPA6-Pad27)") (class "Default")
      (node (ref "IC6") (pin "27") (pinfunction "GPA6_27") (pintype "bidirectional"))
    )
    (net (code "74") (name "unconnected-(IC6-GPA7-Pad28)") (class "Default")
      (node (ref "IC6") (pin "28") (pinfunction "GPA7_28") (pintype "bidirectional"))
    )
    (net (code "75") (name "unconnected-(IC6-GPB6-Pad7)") (class "Default")
      (node (ref "IC6") (pin "7") (pinfunction "GPB6_7") (pintype "bidirectional"))
    )
    (net (code "76") (name "unconnected-(IC6-GPB7-Pad8)") (class "Default")
      (node (ref "IC6") (pin "8") (pinfunction "GPB7_8") (pintype "bidirectional"))
    )
    (net (code "77") (name "unconnected-(IC6-INTA-Pad20)") (class "Default")
      (node (ref "IC6") (pin "20") (pinfunction "INTA_20") (pintype "output"))
    )
    (net (code "78") (name "unconnected-(IC6-INTB-Pad19)") (class "Default")
      (node (ref "IC6") (pin "19") (pinfunction "INTB_19") (pintype "output"))
    )
    (net (code "79") (name "unconnected-(IC8-PB6(OC1B{slash}OC4B{slash}ADC13)-Pad30)") (class "Default")
      (node (ref "IC8") (pin "30") (pinfunction "PB6(OC1B/OC4B/ADC13)_30") (pintype "bidirectional"))
    )
    (net (code "80") (name "unconnected-(IC8-PC6(OC3A{slash}~{OC4A})-Pad31)") (class "Default")
      (node (ref "IC8") (pin "31") (pinfunction "PC6(OC3A/~{OC4A})_31") (pintype "bidirectional"))
    )
    (net (code "81") (name "unconnected-(IC8-PC7(ICP3{slash}CLK0{slash}OC4A)-Pad32)") (class "Default")
      (node (ref "IC8") (pin "32") (pinfunction "PC7(ICP3/CLK0/OC4A)_32") (pintype "bidirectional"))
    )
    (net (code "82") (name "unconnected-(IC8-PE6(INT.6{slash}AIN0)-Pad1)") (class "Default")
      (node (ref "IC8") (pin "1") (pinfunction "PE6(INT.6/AIN0)_1") (pintype "bidirectional"))
    )
    (net (code "83") (name "unconnected-(IC8-PF0(ADC0)-Pad41)") (class "Default")
      (node (ref "IC8") (pin "41") (pinfunction "PF0(ADC0)_41") (pintype "bidirectional"))
    )
    (net (code "84") (name "unconnected-(IC8-PF1(ADC1)-Pad40)") (class "Default")
      (node (ref "IC8") (pin "40") (pinfunction "PF1(ADC1)_40") (pintype "bidirectional"))
    )
    (net (code "85") (name "unconnected-(IC8-PF4(ADC4{slash}TCK)-Pad39)") (class "Default")
      (node (ref "IC8") (pin "39") (pinfunction "PF4(ADC4/TCK)_39") (pintype "bidirectional"))
    )
    (net (code "86") (name "unconnected-(IC8-PF5(ADC5{slash}TMS)-Pad38)") (class "Default")
      (node (ref "IC8") (pin "38") (pinfunction "PF5(ADC5/TMS)_38") (pintype "bidirectional"))
    )
    (net (code "87") (name "unconnected-(IC8-PF6(ADC6{slash}TDO)-Pad37)") (class "Default")
      (node (ref "IC8") (pin "37") (pinfunction "PF6(ADC6/TDO)_37") (pintype "bidirectional"))
    )
    (net (code "88") (name "unconnected-(IC8-PF7(ADC7(TDI)-Pad36)") (class "Default")
      (node (ref "IC8") (pin "36") (pinfunction "PF7(ADC7(TDI)_36") (pintype "bidirectional"))
    )
    (net (code "89") (name "unconnected-(JK1-PadRSH)") (class "Default")
      (node (ref "JK1") (pin "RSH") (pinfunction "RSH_RSH") (pintype "bidirectional"))
    )
    (net (code "90") (name "unconnected-(JK2-PadRSH)") (class "Default")
      (node (ref "JK2") (pin "RSH") (pinfunction "RSH_RSH") (pintype "bidirectional"))
    )
    (net (code "91") (name "unconnected-(JK3-PadRSH)") (class "Default")
      (node (ref "JK3") (pin "RSH") (pinfunction "RSH_RSH") (pintype "bidirectional"))
    )
    (net (code "92") (name "unconnected-(U$1-DIO0-Pad20)") (class "Default")
      (node (ref "U$1") (pin "20") (pinfunction "DIO0_20") (pintype "bidirectional"))
    )
    (net (code "93") (name "unconnected-(U$1-DIO1-Pad19)") (class "Default")
      (node (ref "U$1") (pin "19") (pinfunction "DIO1_19") (pintype "bidirectional"))
    )
    (net (code "94") (name "unconnected-(U$1-DIO2-Pad18)") (class "Default")
      (node (ref "U$1") (pin "18") (pinfunction "DIO2_18") (pintype "bidirectional"))
    )
    (net (code "95") (name "unconnected-(U$1-DIO3-Pad17)") (class "Default")
      (node (ref "U$1") (pin "17") (pinfunction "DIO3_17") (pintype "bidirectional"))
    )
    (net (code "96") (name "unconnected-(U$1-DIO4-Pad11)") (class "Default")
      (node (ref "U$1") (pin "11") (pinfunction "DIO4_11") (pintype "bidirectional"))
    )
    (net (code "97") (name "unconnected-(U$1-DIO5-Pad15)") (class "Default")
      (node (ref "U$1") (pin "15") (pinfunction "DIO5_15") (pintype "bidirectional"))
    )
    (net (code "98") (name "unconnected-(U$1-DIO9-Pad13)") (class "Default")
      (node (ref "U$1") (pin "13") (pinfunction "DIO9_13") (pintype "bidirectional"))
    )
    (net (code "99") (name "unconnected-(U$1-DIO11-Pad7)") (class "Default")
      (node (ref "U$1") (pin "7") (pinfunction "DIO11_7") (pintype "bidirectional"))
    )
    (net (code "100") (name "unconnected-(U$1-DIO12-Pad4)") (class "Default")
      (node (ref "U$1") (pin "4") (pinfunction "DIO12_4") (pintype "bidirectional"))
    )
    (net (code "101") (name "unconnected-(U$1-RES-Pad8)") (class "Default")
      (node (ref "U$1") (pin "8") (pinfunction "RES_8") (pintype "bidirectional"))
    )
    (net (code "102") (name "unconnected-(U$1-RES-Pad14)") (class "Default")
      (node (ref "U$1") (pin "14") (pinfunction "RES_14") (pintype "bidirectional"))
    )
  )
)
